# knxhome-lqfp32.net
KiCad netlist of a schematic drawn in EAGLE
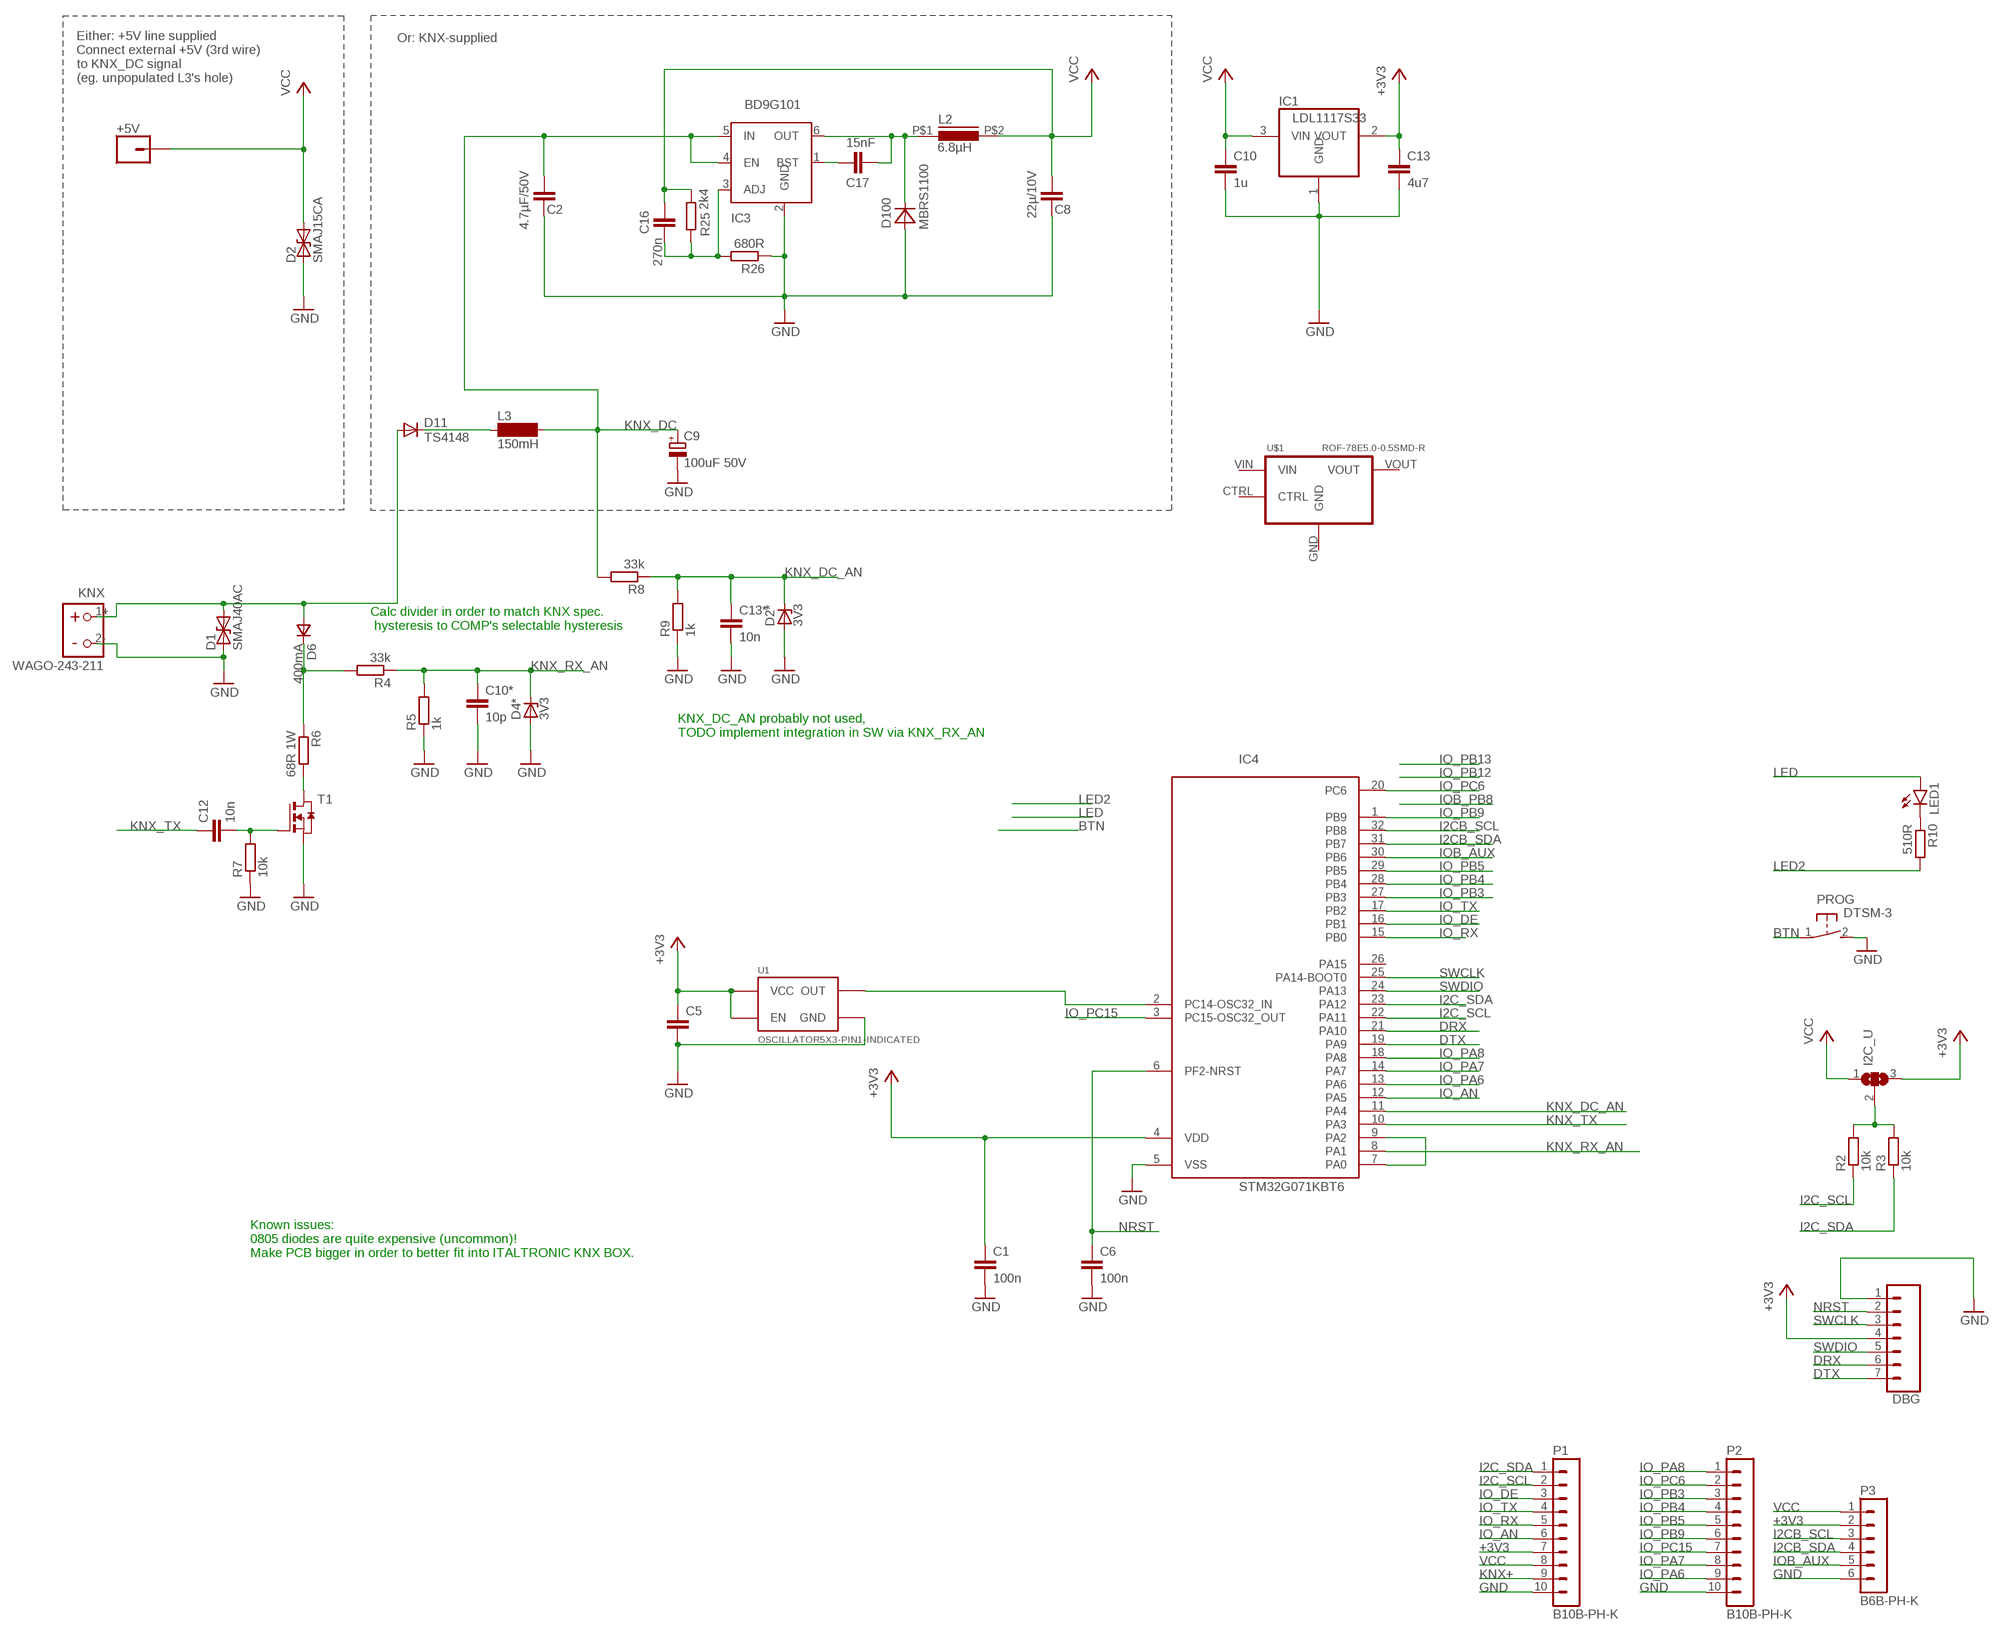
[diagram p0: schematic, sheet 1]

(export (version "E")
  (design (tool "Eeschema 10.0.6"))
  (components
    (comp (ref "+5V")
      (value "CONN_01PTH_LONGPAD")
      (footprint "eagle-import:1X01_LONGPAD")
      (libsource (lib "eagle-import") (part "CONN_01PTH_LONGPAD"))
    )
    (comp (ref "C1")
      (value "100n")
      (footprint "eagle-import:C0805")
      (libsource (lib "eagle-import") (part "C-EUC0805"))
    )
    (comp (ref "C2")
      (value "4.7µF/50V")
      (footprint "eagle-import:C0805")
      (libsource (lib "eagle-import") (part "C-EUC0805"))
    )
    (comp (ref "C5")
      (value "C-EUC0805")
      (footprint "eagle-import:C0805")
      (libsource (lib "eagle-import") (part "C-EUC0805"))
    )
    (comp (ref "C6")
      (value "100n")
      (footprint "eagle-import:C0805")
      (libsource (lib "eagle-import") (part "C-EUC0805"))
    )
    (comp (ref "C8")
      (value "22µ/10V")
      (footprint "eagle-import:C0805")
      (libsource (lib "eagle-import") (part "C-EUC0805"))
    )
    (comp (ref "C9")
      (value "100uF 50V")
      (footprint "eagle-import:E3,5-8")
      (libsource (lib "eagle-import") (part "CPOL-EUE3.5-8"))
    )
    (comp (ref "C10")
      (value "1u")
      (footprint "eagle-import:C0805")
      (libsource (lib "eagle-import") (part "C-EUC0805"))
    )
    (comp (ref "C10*")
      (value "10p")
      (footprint "eagle-import:C0805")
      (libsource (lib "eagle-import") (part "C-EUC0805"))
    )
    (comp (ref "C12")
      (value "10n")
      (footprint "eagle-import:C0805")
      (libsource (lib "eagle-import") (part "C-EUC0805"))
    )
    (comp (ref "C13")
      (value "4u7")
      (footprint "eagle-import:C0805")
      (libsource (lib "eagle-import") (part "C-EUC0805"))
    )
    (comp (ref "C13*")
      (value "10n")
      (footprint "eagle-import:C0805")
      (libsource (lib "eagle-import") (part "C-EUC0805"))
    )
    (comp (ref "C16")
      (value "270n")
      (footprint "eagle-import:C0805")
      (libsource (lib "eagle-import") (part "C-EUC0805"))
    )
    (comp (ref "C17")
      (value "15nF")
      (footprint "eagle-import:C0805")
      (libsource (lib "eagle-import") (part "C-EUC0805"))
    )
    (comp (ref "D1")
      (value "SMAJ40AC")
      (footprint "eagle-import:DO-214AC")
      (libsource (lib "eagle-import") (part "SMAJ40AC"))
    )
    (comp (ref "D2")
      (value "SMAJ15CA")
      (footprint "eagle-import:DO-214AC")
      (libsource (lib "eagle-import") (part "SMAJ40AC"))
    )
    (comp (ref "D2*")
      (value "3V3")
      (footprint "eagle-import:SOT23")
      (libsource (lib "eagle-import") (part "ZENER-DIODESOT23"))
    )
    (comp (ref "D4*")
      (value "3V3")
      (footprint "eagle-import:SOT23")
      (libsource (lib "eagle-import") (part "ZENER-DIODESOT23"))
    )
    (comp (ref "D6")
      (value "400mA")
      (footprint "eagle-import:SOD323")
      (fields (field (name "MPN") "CDSOD323-T05C"))
      (libsource (lib "eagle-import") (part "DSOD323"))
    )
    (comp (ref "D11")
      (value "TS4148")
      (footprint "eagle-import:D0805")
      (libsource (lib "eagle-import") (part "DIODE-D0805"))
    )
    (comp (ref "D100")
      (value "MBRS1100")
      (footprint "eagle-import:SMA")
      (libsource (lib "eagle-import") (part "MBRA340T3"))
    )
    (comp (ref "DBG")
      (value "CONN_07LOCK")
      (footprint "eagle-import:1X07_LOCK")
      (libsource (lib "eagle-import") (part "CONN_07LOCK"))
    )
    (comp (ref "I2C_U")
      (value "SJ2W")
      (footprint "eagle-import:SJ_2")
      (libsource (lib "eagle-import") (part "SJ2W"))
    )
    (comp (ref "IC1")
      (value "LDL1117S33")
      (footprint "eagle-import:SOT223")
      (fields (field (name "MPN") "REG1117"))
      (libsource (lib "eagle-import") (part "REG1117"))
    )
    (comp (ref "IC3")
      (value "BD9G101")
      (footprint "eagle-import:SOT23-6")
      (libsource (lib "eagle-import") (part "BD9G101GBD9G101G-SOT23-6"))
    )
    (comp (ref "IC4")
      (value "STM32G071KBT6")
      (footprint "eagle-import:LQFP32")
      (libsource (lib "eagle-import") (part "STM32G071KBT6"))
    )
    (comp (ref "KNX")
      (value "WAGO-243-211")
      (footprint "eagle-import:WAGO-243-211")
      (libsource (lib "eagle-import") (part "WAGO-243-211"))
    )
    (comp (ref "L2")
      (value "6.8µH")
      (footprint "eagle-import:PIS2812")
      (libsource (lib "eagle-import") (part "IND_FASTRON_1616FPS"))
    )
    (comp (ref "L3")
      (value "150mH")
      (footprint "eagle-import:BS11_LIEGEND")
      (libsource (lib "eagle-import") (part "SD12BS11_LIEGEND"))
    )
    (comp (ref "LED1")
      (value "LEDCHIP-LED0805")
      (footprint "eagle-import:CHIP-LED0805")
      (libsource (lib "eagle-import") (part "LEDCHIP-LED0805"))
    )
    (comp (ref "P1")
      (value "B10B-PH-K")
      (footprint "eagle-import:B10B-PH-K")
      (libsource (lib "eagle-import") (part "B10B-PH-K"))
    )
    (comp (ref "P2")
      (value "B10B-PH-K")
      (footprint "eagle-import:B10B-PH-K")
      (libsource (lib "eagle-import") (part "B10B-PH-K"))
    )
    (comp (ref "P3")
      (value "B6B-PH-K")
      (footprint "eagle-import:B6B-PH-K")
      (libsource (lib "eagle-import") (part "B6B-PH-K"))
    )
    (comp (ref "PROG")
      (value "DTSM-3")
      (footprint "eagle-import:DTSM-3")
      (libsource (lib "eagle-import") (part "DTSM-3"))
    )
    (comp (ref "R2")
      (value "10k")
      (footprint "eagle-import:R0805")
      (libsource (lib "eagle-import") (part "R-EU_R0805"))
    )
    (comp (ref "R3")
      (value "10k")
      (footprint "eagle-import:R0805")
      (libsource (lib "eagle-import") (part "R-EU_R0805"))
    )
    (comp (ref "R4")
      (value "33k")
      (footprint "eagle-import:R0805")
      (libsource (lib "eagle-import") (part "R-EU_R0805"))
    )
    (comp (ref "R5")
      (value "1k")
      (footprint "eagle-import:R0805")
      (libsource (lib "eagle-import") (part "R-EU_R0805"))
    )
    (comp (ref "R6")
      (value "68R 1W")
      (footprint "eagle-import:R2512")
      (libsource (lib "eagle-import") (part "R-EU_R2512"))
    )
    (comp (ref "R7")
      (value "10k")
      (footprint "eagle-import:R0805")
      (libsource (lib "eagle-import") (part "R-EU_R0805"))
    )
    (comp (ref "R8")
      (value "33k")
      (footprint "eagle-import:R0805")
      (libsource (lib "eagle-import") (part "R-EU_R0805"))
    )
    (comp (ref "R9")
      (value "1k")
      (footprint "eagle-import:R0805")
      (libsource (lib "eagle-import") (part "R-EU_R0805"))
    )
    (comp (ref "R10")
      (value "510R")
      (footprint "eagle-import:R0805")
      (libsource (lib "eagle-import") (part "R-EU_R0805"))
    )
    (comp (ref "R25")
      (value "2k4")
      (footprint "eagle-import:R0805")
      (libsource (lib "eagle-import") (part "R-EU_R0805"))
    )
    (comp (ref "R26")
      (value "680R")
      (footprint "eagle-import:R0805")
      (libsource (lib "eagle-import") (part "R-EU_R0805"))
    )
    (comp (ref "T1")
      (value "NMOSSOT23")
      (footprint "eagle-import:SOT-23")
      (libsource (lib "eagle-import") (part "NMOSSOT23"))
    )
    (comp (ref "U$1")
      (value "ROF-78E5.0-0.5SMD-R")
      (footprint "eagle-import:ROF-78EX-XSMD-R")
      (libsource (lib "eagle-import") (part "ROF-78E5.0-0.5SMD-R"))
    )
    (comp (ref "U1")
      (value "OSCILLATOR5X3-PIN1-INDICATED")
      (footprint "eagle-import:CRYSTAL-OSC-SMD-5X3")
      (libsource (lib "eagle-import") (part "OSCILLATOR5X3-PIN1-INDICATED"))
    )
  )
  (nets
    (net (code "1") (name "+3V3") (class "Default")
      (node (ref "C1") (pin "1") (pinfunction "1_1") (pintype "passive"))
      (node (ref "C13") (pin "1") (pinfunction "1_1") (pintype "passive"))
      (node (ref "C5") (pin "1") (pinfunction "1_1") (pintype "passive"))
      (node (ref "DBG") (pin "4") (pinfunction "4_4") (pintype "passive"))
      (node (ref "I2C_U") (pin "3") (pinfunction "3_3") (pintype "passive"))
      (node (ref "IC1") (pin "2") (pinfunction "VOUT_2") (pintype "output"))
      (node (ref "IC4") (pin "4") (pinfunction "VDD_4") (pintype "power_in"))
      (node (ref "P1") (pin "7") (pinfunction "7_7") (pintype "passive"))
      (node (ref "P3") (pin "2") (pinfunction "2_2") (pintype "passive"))
      (node (ref "U1") (pin "1") (pinfunction "EN_1") (pintype "bidirectional"))
      (node (ref "U1") (pin "4") (pinfunction "VCC_4") (pintype "bidirectional"))
    )
    (net (code "2") (name "/BTN") (class "Default")
      (node (ref "PROG") (pin "1") (pinfunction "1_1") (pintype "passive"))
    )
    (net (code "3") (name "/DRX") (class "Default")
      (node (ref "DBG") (pin "6") (pinfunction "6_6") (pintype "passive"))
      (node (ref "IC4") (pin "21") (pinfunction "PA10_21") (pintype "bidirectional"))
    )
    (net (code "4") (name "/DTX") (class "Default")
      (node (ref "DBG") (pin "7") (pinfunction "7_7") (pintype "passive"))
      (node (ref "IC4") (pin "19") (pinfunction "PA9_19") (pintype "bidirectional"))
    )
    (net (code "5") (name "/I2CB_SCL") (class "Default")
      (node (ref "IC4") (pin "32") (pinfunction "PB8_32") (pintype "bidirectional"))
      (node (ref "P3") (pin "3") (pinfunction "3_3") (pintype "passive"))
    )
    (net (code "6") (name "/I2CB_SDA") (class "Default")
      (node (ref "IC4") (pin "31") (pinfunction "PB7_31") (pintype "bidirectional"))
      (node (ref "P3") (pin "4") (pinfunction "4_4") (pintype "passive"))
    )
    (net (code "7") (name "/I2C_SCL") (class "Default")
      (node (ref "IC4") (pin "22") (pinfunction "PA11_22") (pintype "bidirectional"))
      (node (ref "P1") (pin "2") (pinfunction "2_2") (pintype "passive"))
      (node (ref "R2") (pin "1") (pinfunction "1_1") (pintype "passive"))
    )
    (net (code "8") (name "/I2C_SDA") (class "Default")
      (node (ref "IC4") (pin "23") (pinfunction "PA12_23") (pintype "bidirectional"))
      (node (ref "P1") (pin "1") (pinfunction "1_1") (pintype "passive"))
      (node (ref "R3") (pin "1") (pinfunction "1_1") (pintype "passive"))
    )
    (net (code "9") (name "/IOB_AUX") (class "Default")
      (node (ref "IC4") (pin "30") (pinfunction "PB6_30") (pintype "bidirectional"))
      (node (ref "P3") (pin "5") (pinfunction "5_5") (pintype "passive"))
    )
    (net (code "11") (name "/IO_AN") (class "Default")
      (node (ref "IC4") (pin "12") (pinfunction "PA5_12") (pintype "bidirectional"))
      (node (ref "P1") (pin "6") (pinfunction "6_6") (pintype "passive"))
    )
    (net (code "12") (name "/IO_DE") (class "Default")
      (node (ref "IC4") (pin "16") (pinfunction "PB1_16") (pintype "bidirectional"))
      (node (ref "P1") (pin "3") (pinfunction "3_3") (pintype "passive"))
    )
    (net (code "13") (name "/IO_PA6") (class "Default")
      (node (ref "IC4") (pin "13") (pinfunction "PA6_13") (pintype "bidirectional"))
      (node (ref "P2") (pin "9") (pinfunction "9_9") (pintype "passive"))
    )
    (net (code "14") (name "/IO_PA7") (class "Default")
      (node (ref "IC4") (pin "14") (pinfunction "PA7_14") (pintype "bidirectional"))
      (node (ref "P2") (pin "8") (pinfunction "8_8") (pintype "passive"))
    )
    (net (code "15") (name "/IO_PA8") (class "Default")
      (node (ref "IC4") (pin "18") (pinfunction "PA8_18") (pintype "bidirectional"))
      (node (ref "P2") (pin "1") (pinfunction "1_1") (pintype "passive"))
    )
    (net (code "16") (name "/IO_PB3") (class "Default")
      (node (ref "IC4") (pin "27") (pinfunction "PB3_27") (pintype "bidirectional"))
      (node (ref "P2") (pin "3") (pinfunction "3_3") (pintype "passive"))
    )
    (net (code "17") (name "/IO_PB4") (class "Default")
      (node (ref "IC4") (pin "28") (pinfunction "PB4_28") (pintype "bidirectional"))
      (node (ref "P2") (pin "4") (pinfunction "4_4") (pintype "passive"))
    )
    (net (code "18") (name "/IO_PB5") (class "Default")
      (node (ref "IC4") (pin "29") (pinfunction "PB5_29") (pintype "bidirectional"))
      (node (ref "P2") (pin "5") (pinfunction "5_5") (pintype "passive"))
    )
    (net (code "19") (name "/IO_PB9") (class "Default")
      (node (ref "IC4") (pin "1") (pinfunction "PB9_1") (pintype "bidirectional"))
      (node (ref "P2") (pin "6") (pinfunction "6_6") (pintype "passive"))
    )
    (net (code "22") (name "/IO_PC6") (class "Default")
      (node (ref "IC4") (pin "20") (pinfunction "PC6_20") (pintype "bidirectional"))
      (node (ref "P2") (pin "2") (pinfunction "2_2") (pintype "passive"))
    )
    (net (code "23") (name "/IO_PC15") (class "Default")
      (node (ref "IC4") (pin "3") (pinfunction "PC15-OSC32_OUT_3") (pintype "bidirectional"))
      (node (ref "P2") (pin "7") (pinfunction "7_7") (pintype "passive"))
    )
    (net (code "24") (name "/IO_RX") (class "Default")
      (node (ref "IC4") (pin "15") (pinfunction "PB0_15") (pintype "bidirectional"))
      (node (ref "P1") (pin "5") (pinfunction "5_5") (pintype "passive"))
    )
    (net (code "25") (name "/IO_TX") (class "Default")
      (node (ref "IC4") (pin "17") (pinfunction "PB2_17") (pintype "bidirectional"))
      (node (ref "P1") (pin "4") (pinfunction "4_4") (pintype "passive"))
    )
    (net (code "26") (name "/KNX+") (class "Default")
      (node (ref "D1") (pin "C") (pinfunction "C_C") (pintype "passive"))
      (node (ref "D11") (pin "A") (pinfunction "A_A") (pintype "passive"))
      (node (ref "D6") (pin "2") (pinfunction "A_2") (pintype "passive"))
      (node (ref "KNX") (pin "1+") (pinfunction "1+_1+") (pintype "passive"))
      (node (ref "P1") (pin "9") (pinfunction "9_9") (pintype "passive"))
    )
    (net (code "27") (name "/KNX_DC") (class "Default")
      (node (ref "C2") (pin "2") (pinfunction "2_2") (pintype "passive"))
      (node (ref "C9") (pin "+") (pinfunction "+_+") (pintype "passive"))
      (node (ref "IC3") (pin "4") (pinfunction "EN_4") (pintype "input"))
      (node (ref "IC3") (pin "5") (pinfunction "IN_5") (pintype "input"))
      (node (ref "L3") (pin "2") (pinfunction "2_2") (pintype "passive"))
      (node (ref "R8") (pin "2") (pinfunction "2_2") (pintype "passive"))
    )
    (net (code "28") (name "/KNX_DC_AN") (class "Default")
      (node (ref "C13*") (pin "1") (pinfunction "1_1") (pintype "passive"))
      (node (ref "D2*") (pin "3") (pinfunction "C_3") (pintype "passive"))
      (node (ref "IC4") (pin "11") (pinfunction "PA4_11") (pintype "bidirectional"))
      (node (ref "R8") (pin "1") (pinfunction "1_1") (pintype "passive"))
      (node (ref "R9") (pin "2") (pinfunction "2_2") (pintype "passive"))
    )
    (net (code "29") (name "/KNX_RX_AN") (class "Default")
      (node (ref "C10*") (pin "1") (pinfunction "1_1") (pintype "passive"))
      (node (ref "D4*") (pin "3") (pinfunction "C_3") (pintype "passive"))
      (node (ref "IC4") (pin "8") (pinfunction "PA1_8") (pintype "bidirectional"))
      (node (ref "R4") (pin "1") (pinfunction "1_1") (pintype "passive"))
      (node (ref "R5") (pin "2") (pinfunction "2_2") (pintype "passive"))
    )
    (net (code "30") (name "/KNX_TX") (class "Default")
      (node (ref "C12") (pin "1") (pinfunction "1_1") (pintype "passive"))
      (node (ref "IC4") (pin "10") (pinfunction "PA3_10") (pintype "bidirectional"))
    )
    (net (code "31") (name "/LED") (class "Default")
      (node (ref "LED1") (pin "A") (pinfunction "A_A") (pintype "passive"))
    )
    (net (code "32") (name "/LED2") (class "Default")
      (node (ref "R10") (pin "2") (pinfunction "2_2") (pintype "passive"))
    )
    (net (code "33") (name "/NRST") (class "Default")
      (node (ref "C6") (pin "1") (pinfunction "1_1") (pintype "passive"))
      (node (ref "DBG") (pin "2") (pinfunction "2_2") (pintype "passive"))
      (node (ref "IC4") (pin "6") (pinfunction "PF2-NRST_6") (pintype "bidirectional"))
    )
    (net (code "34") (name "/SWCLK") (class "Default")
      (node (ref "DBG") (pin "3") (pinfunction "3_3") (pintype "passive"))
      (node (ref "IC4") (pin "25") (pinfunction "PA14-BOOT0_25") (pintype "bidirectional"))
    )
    (net (code "35") (name "/SWDIO") (class "Default")
      (node (ref "DBG") (pin "5") (pinfunction "5_5") (pintype "passive"))
      (node (ref "IC4") (pin "24") (pinfunction "PA13_24") (pintype "bidirectional"))
    )
    (net (code "36") (name "GND") (class "Default")
      (node (ref "C1") (pin "2") (pinfunction "2_2") (pintype "passive"))
      (node (ref "C10") (pin "2") (pinfunction "2_2") (pintype "passive"))
      (node (ref "C10*") (pin "2") (pinfunction "2_2") (pintype "passive"))
      (node (ref "C13") (pin "2") (pinfunction "2_2") (pintype "passive"))
      (node (ref "C13*") (pin "2") (pinfunction "2_2") (pintype "passive"))
      (node (ref "C2") (pin "1") (pinfunction "1_1") (pintype "passive"))
      (node (ref "C5") (pin "2") (pinfunction "2_2") (pintype "passive"))
      (node (ref "C6") (pin "2") (pinfunction "2_2") (pintype "passive"))
      (node (ref "C8") (pin "1") (pinfunction "1_1") (pintype "passive"))
      (node (ref "C9") (pin "-") (pinfunction "-_-") (pintype "passive"))
      (node (ref "D1") (pin "A") (pinfunction "A_A") (pintype "passive"))
      (node (ref "D100") (pin "A") (pinfunction "A_A") (pintype "passive"))
      (node (ref "D2") (pin "A") (pinfunction "A_A") (pintype "passive"))
      (node (ref "D2*") (pin "1") (pinfunction "A_1") (pintype "passive"))
      (node (ref "D4*") (pin "1") (pinfunction "A_1") (pintype "passive"))
      (node (ref "DBG") (pin "1") (pinfunction "1_1") (pintype "passive"))
      (node (ref "IC1") (pin "1") (pinfunction "GND_1") (pintype "power_in"))
      (node (ref "IC3") (pin "2") (pinfunction "GND_2") (pintype "power_in"))
      (node (ref "IC4") (pin "5") (pinfunction "VSS_5") (pintype "power_in"))
      (node (ref "KNX") (pin "2-") (pinfunction "2-_2-") (pintype "passive"))
      (node (ref "P1") (pin "10") (pinfunction "10_10") (pintype "passive"))
      (node (ref "P2") (pin "10") (pinfunction "10_10") (pintype "passive"))
      (node (ref "P3") (pin "6") (pinfunction "6_6") (pintype "passive"))
      (node (ref "PROG") (pin "2") (pinfunction "2_2") (pintype "passive"))
      (node (ref "R26") (pin "1") (pinfunction "1_1") (pintype "passive"))
      (node (ref "R5") (pin "1") (pinfunction "1_1") (pintype "passive"))
      (node (ref "R7") (pin "1") (pinfunction "1_1") (pintype "passive"))
      (node (ref "R9") (pin "1") (pinfunction "1_1") (pintype "passive"))
      (node (ref "T1") (pin "2") (pinfunction "S_2") (pintype "passive"))
      (node (ref "U1") (pin "2") (pinfunction "GND_2") (pintype "bidirectional"))
    )
    (net (code "37") (name "Net-(D6-C)") (class "Default")
      (node (ref "D6") (pin "1") (pinfunction "C_1") (pintype "passive"))
      (node (ref "R4") (pin "2") (pinfunction "2_2") (pintype "passive"))
      (node (ref "R6") (pin "1") (pinfunction "1_1") (pintype "passive"))
    )
    (net (code "38") (name "Net-(D11-PadC)") (class "Default")
      (node (ref "D11") (pin "C") (pinfunction "C_C") (pintype "passive"))
      (node (ref "L3") (pin "1") (pinfunction "1_1") (pintype "passive"))
    )
    (net (code "39") (name "Net-(I2C_U-Pad2)") (class "Default")
      (node (ref "I2C_U") (pin "2") (pinfunction "2_2") (pintype "passive"))
      (node (ref "R2") (pin "2") (pinfunction "2_2") (pintype "passive"))
      (node (ref "R3") (pin "2") (pinfunction "2_2") (pintype "passive"))
    )
    (net (code "40") (name "Net-(IC3-ADJ)") (class "Default")
      (node (ref "C16") (pin "1") (pinfunction "1_1") (pintype "passive"))
      (node (ref "IC3") (pin "3") (pinfunction "ADJ_3") (pintype "passive"))
      (node (ref "R25") (pin "1") (pinfunction "1_1") (pintype "passive"))
      (node (ref "R26") (pin "2") (pinfunction "2_2") (pintype "passive"))
    )
    (net (code "41") (name "Net-(IC3-BST)") (class "Default")
      (node (ref "C17") (pin "2") (pinfunction "2_2") (pintype "passive"))
      (node (ref "IC3") (pin "1") (pinfunction "BST_1") (pintype "output"))
    )
    (net (code "42") (name "Net-(IC3-OUT)") (class "Default")
      (node (ref "C17") (pin "1") (pinfunction "1_1") (pintype "passive"))
      (node (ref "D100") (pin "C") (pinfunction "C_C") (pintype "passive"))
      (node (ref "IC3") (pin "6") (pinfunction "OUT_6") (pintype "output"))
      (node (ref "L2") (pin "P$1") (pinfunction "1_P$1") (pintype "passive"))
    )
    (net (code "43") (name "Net-(IC4-PA0)") (class "Default")
      (node (ref "IC4") (pin "7") (pinfunction "PA0_7") (pintype "bidirectional"))
      (node (ref "IC4") (pin "9") (pinfunction "PA2_9") (pintype "bidirectional"))
    )
    (net (code "44") (name "Net-(IC4-PC14-OSC32_IN)") (class "Default")
      (node (ref "IC4") (pin "2") (pinfunction "PC14-OSC32_IN_2") (pintype "bidirectional"))
      (node (ref "U1") (pin "3") (pinfunction "OUT_3") (pintype "bidirectional"))
    )
    (net (code "45") (name "Net-(LED1-PadC)") (class "Default")
      (node (ref "LED1") (pin "C") (pinfunction "C_C") (pintype "passive"))
      (node (ref "R10") (pin "1") (pinfunction "1_1") (pintype "passive"))
    )
    (net (code "46") (name "Net-(T1-D)") (class "Default")
      (node (ref "R6") (pin "2") (pinfunction "2_2") (pintype "passive"))
      (node (ref "T1") (pin "1") (pinfunction "D_1") (pintype "passive"))
    )
    (net (code "47") (name "Net-(T1-G)") (class "Default")
      (node (ref "C12") (pin "2") (pinfunction "2_2") (pintype "passive"))
      (node (ref "R7") (pin "2") (pinfunction "2_2") (pintype "passive"))
      (node (ref "T1") (pin "3") (pinfunction "G_3") (pintype "passive"))
    )
    (net (code "48") (name "VCC") (class "Default")
      (node (ref "+5V") (pin "1") (pinfunction "1_1") (pintype "passive"))
      (node (ref "C10") (pin "1") (pinfunction "1_1") (pintype "passive"))
      (node (ref "C16") (pin "2") (pinfunction "2_2") (pintype "passive"))
      (node (ref "C8") (pin "2") (pinfunction "2_2") (pintype "passive"))
      (node (ref "D2") (pin "C") (pinfunction "C_C") (pintype "passive"))
      (node (ref "I2C_U") (pin "1") (pinfunction "1_1") (pintype "passive"))
      (node (ref "IC1") (pin "3") (pinfunction "VIN_3") (pintype "input"))
      (node (ref "L2") (pin "P$2") (pinfunction "2_P$2") (pintype "passive"))
      (node (ref "P1") (pin "8") (pinfunction "8_8") (pintype "passive"))
      (node (ref "P3") (pin "1") (pinfunction "1_1") (pintype "passive"))
      (node (ref "R25") (pin "2") (pinfunction "2_2") (pintype "passive"))
    )
    (net (code "49") (name "unconnected-(IC4-PA15-Pad26)") (class "Default")
      (node (ref "IC4") (pin "26") (pinfunction "PA15_26") (pintype "bidirectional"))
    )
    (net (code "50") (name "unconnected-(U$1-PadCTRL)") (class "Default")
      (node (ref "U$1") (pin "CTRL") (pinfunction "CTRL_CTRL") (pintype "bidirectional"))
    )
    (net (code "51") (name "unconnected-(U$1-PadGND)") (class "Default")
      (node (ref "U$1") (pin "GND") (pinfunction "GND_GND") (pintype "bidirectional"))
    )
    (net (code "52") (name "unconnected-(U$1-PadVIN)") (class "Default")
      (node (ref "U$1") (pin "VIN") (pinfunction "VIN_VIN") (pintype "bidirectional"))
    )
    (net (code "53") (name "unconnected-(U$1-PadVOUT)") (class "Default")
      (node (ref "U$1") (pin "VOUT") (pinfunction "VOUT_VOUT") (pintype "bidirectional"))
    )
  )
)
